# tdt_cableTester.net
KiCad netlist of a schematic drawn in EAGLE
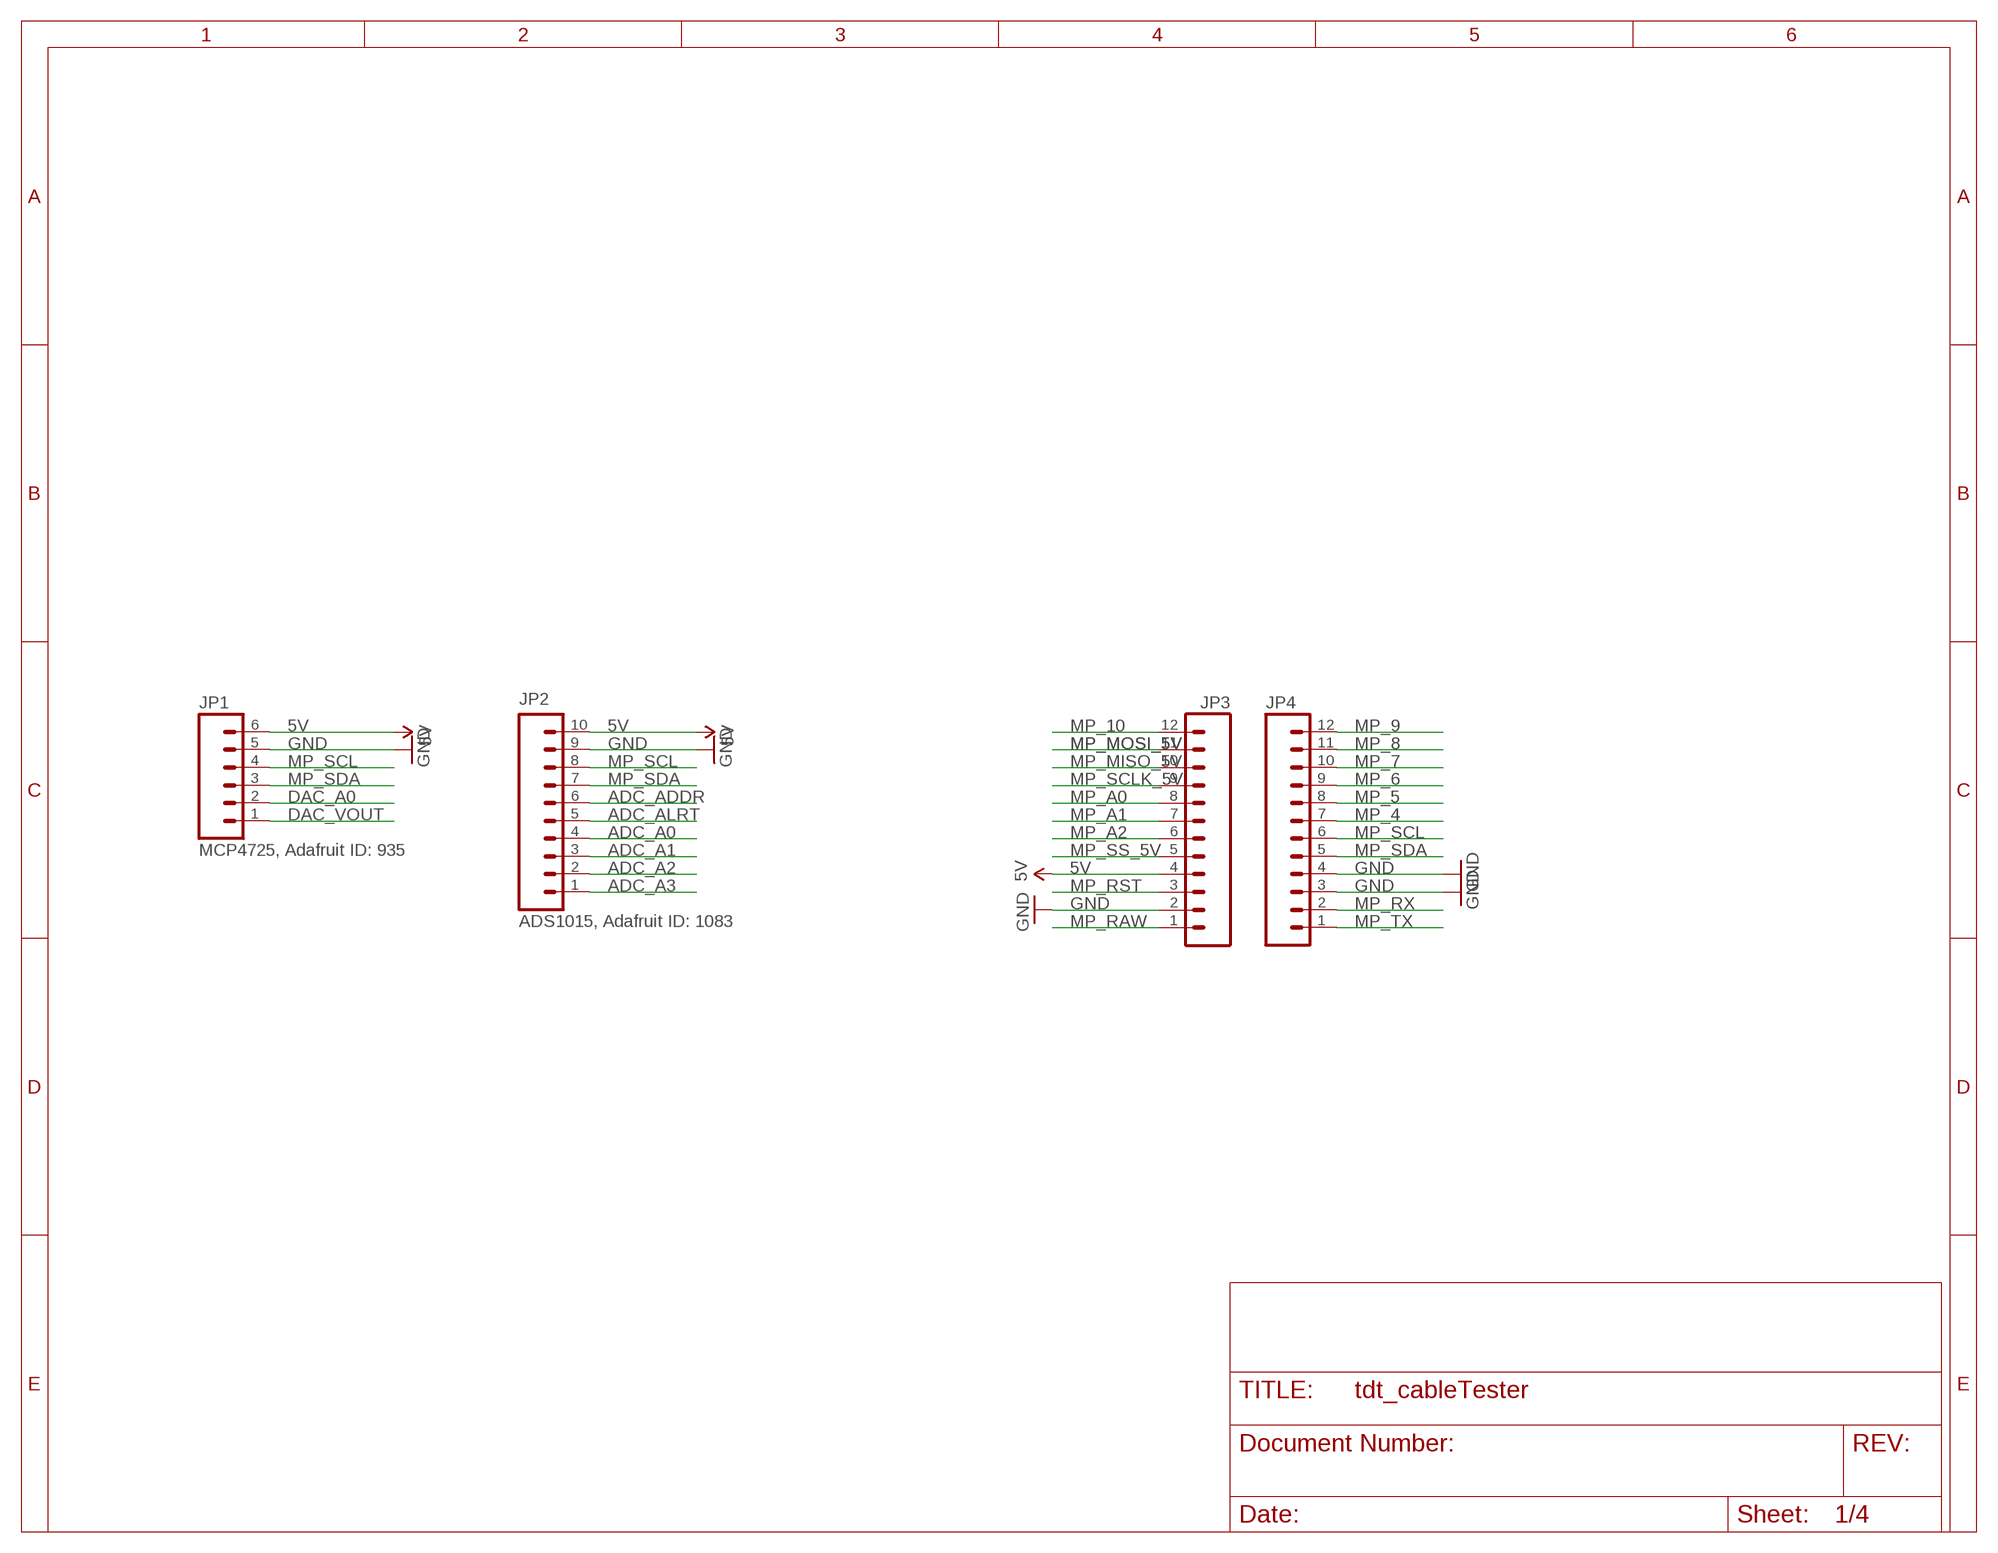
[diagram p0: schematic, sheet 1]
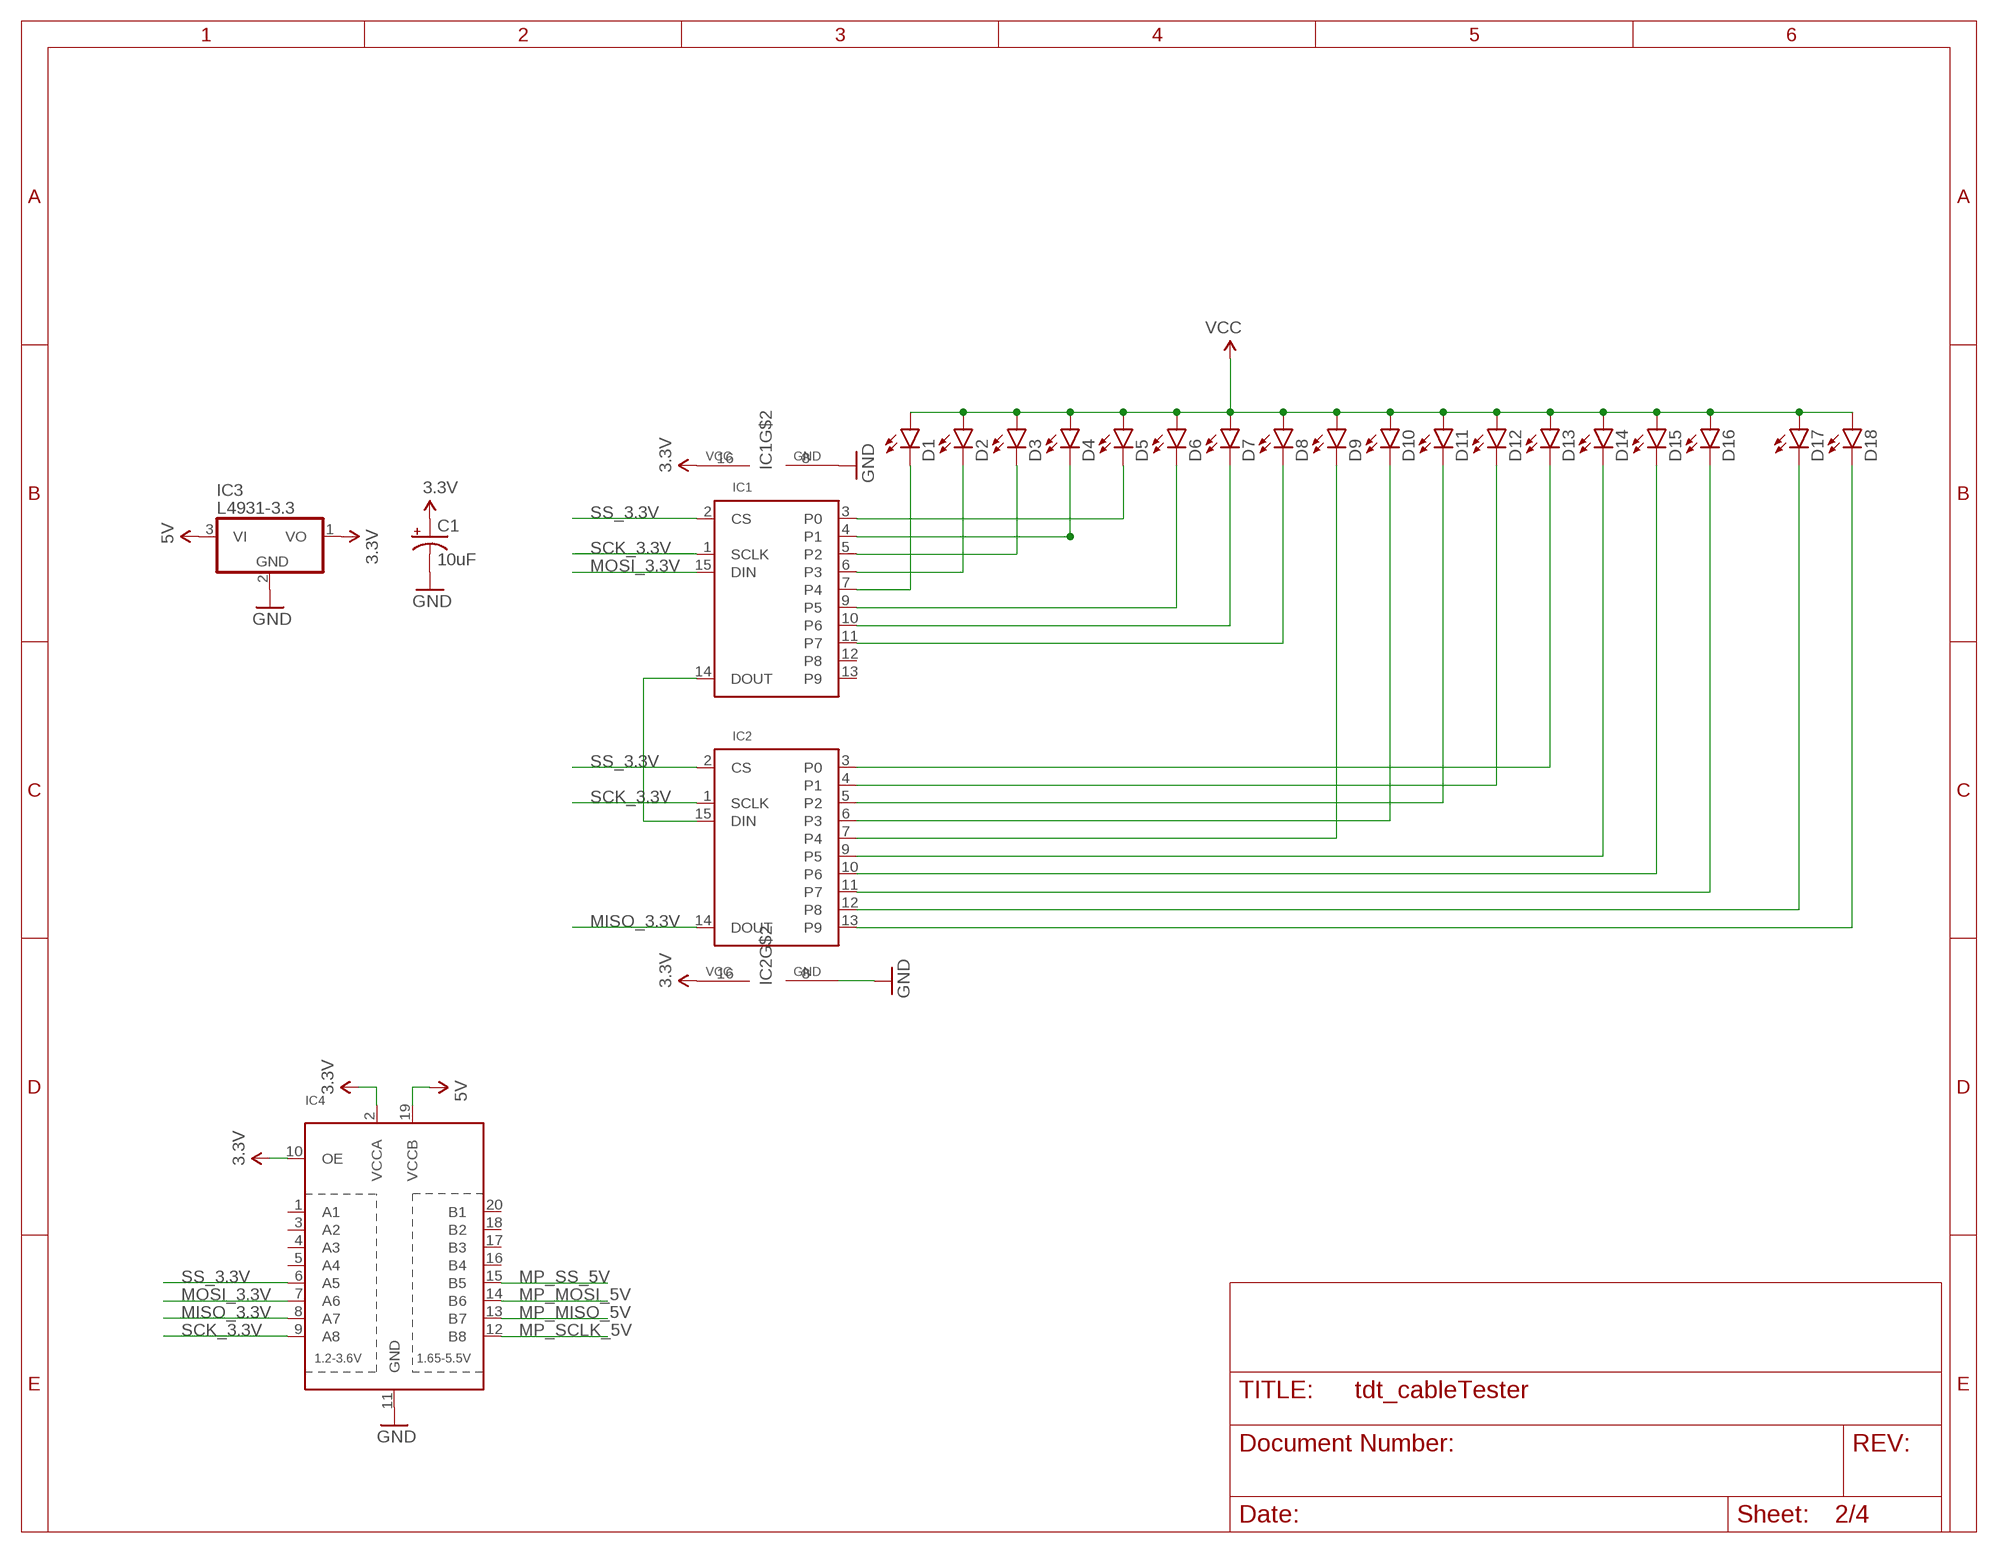
[diagram p1: schematic, sheet 2]
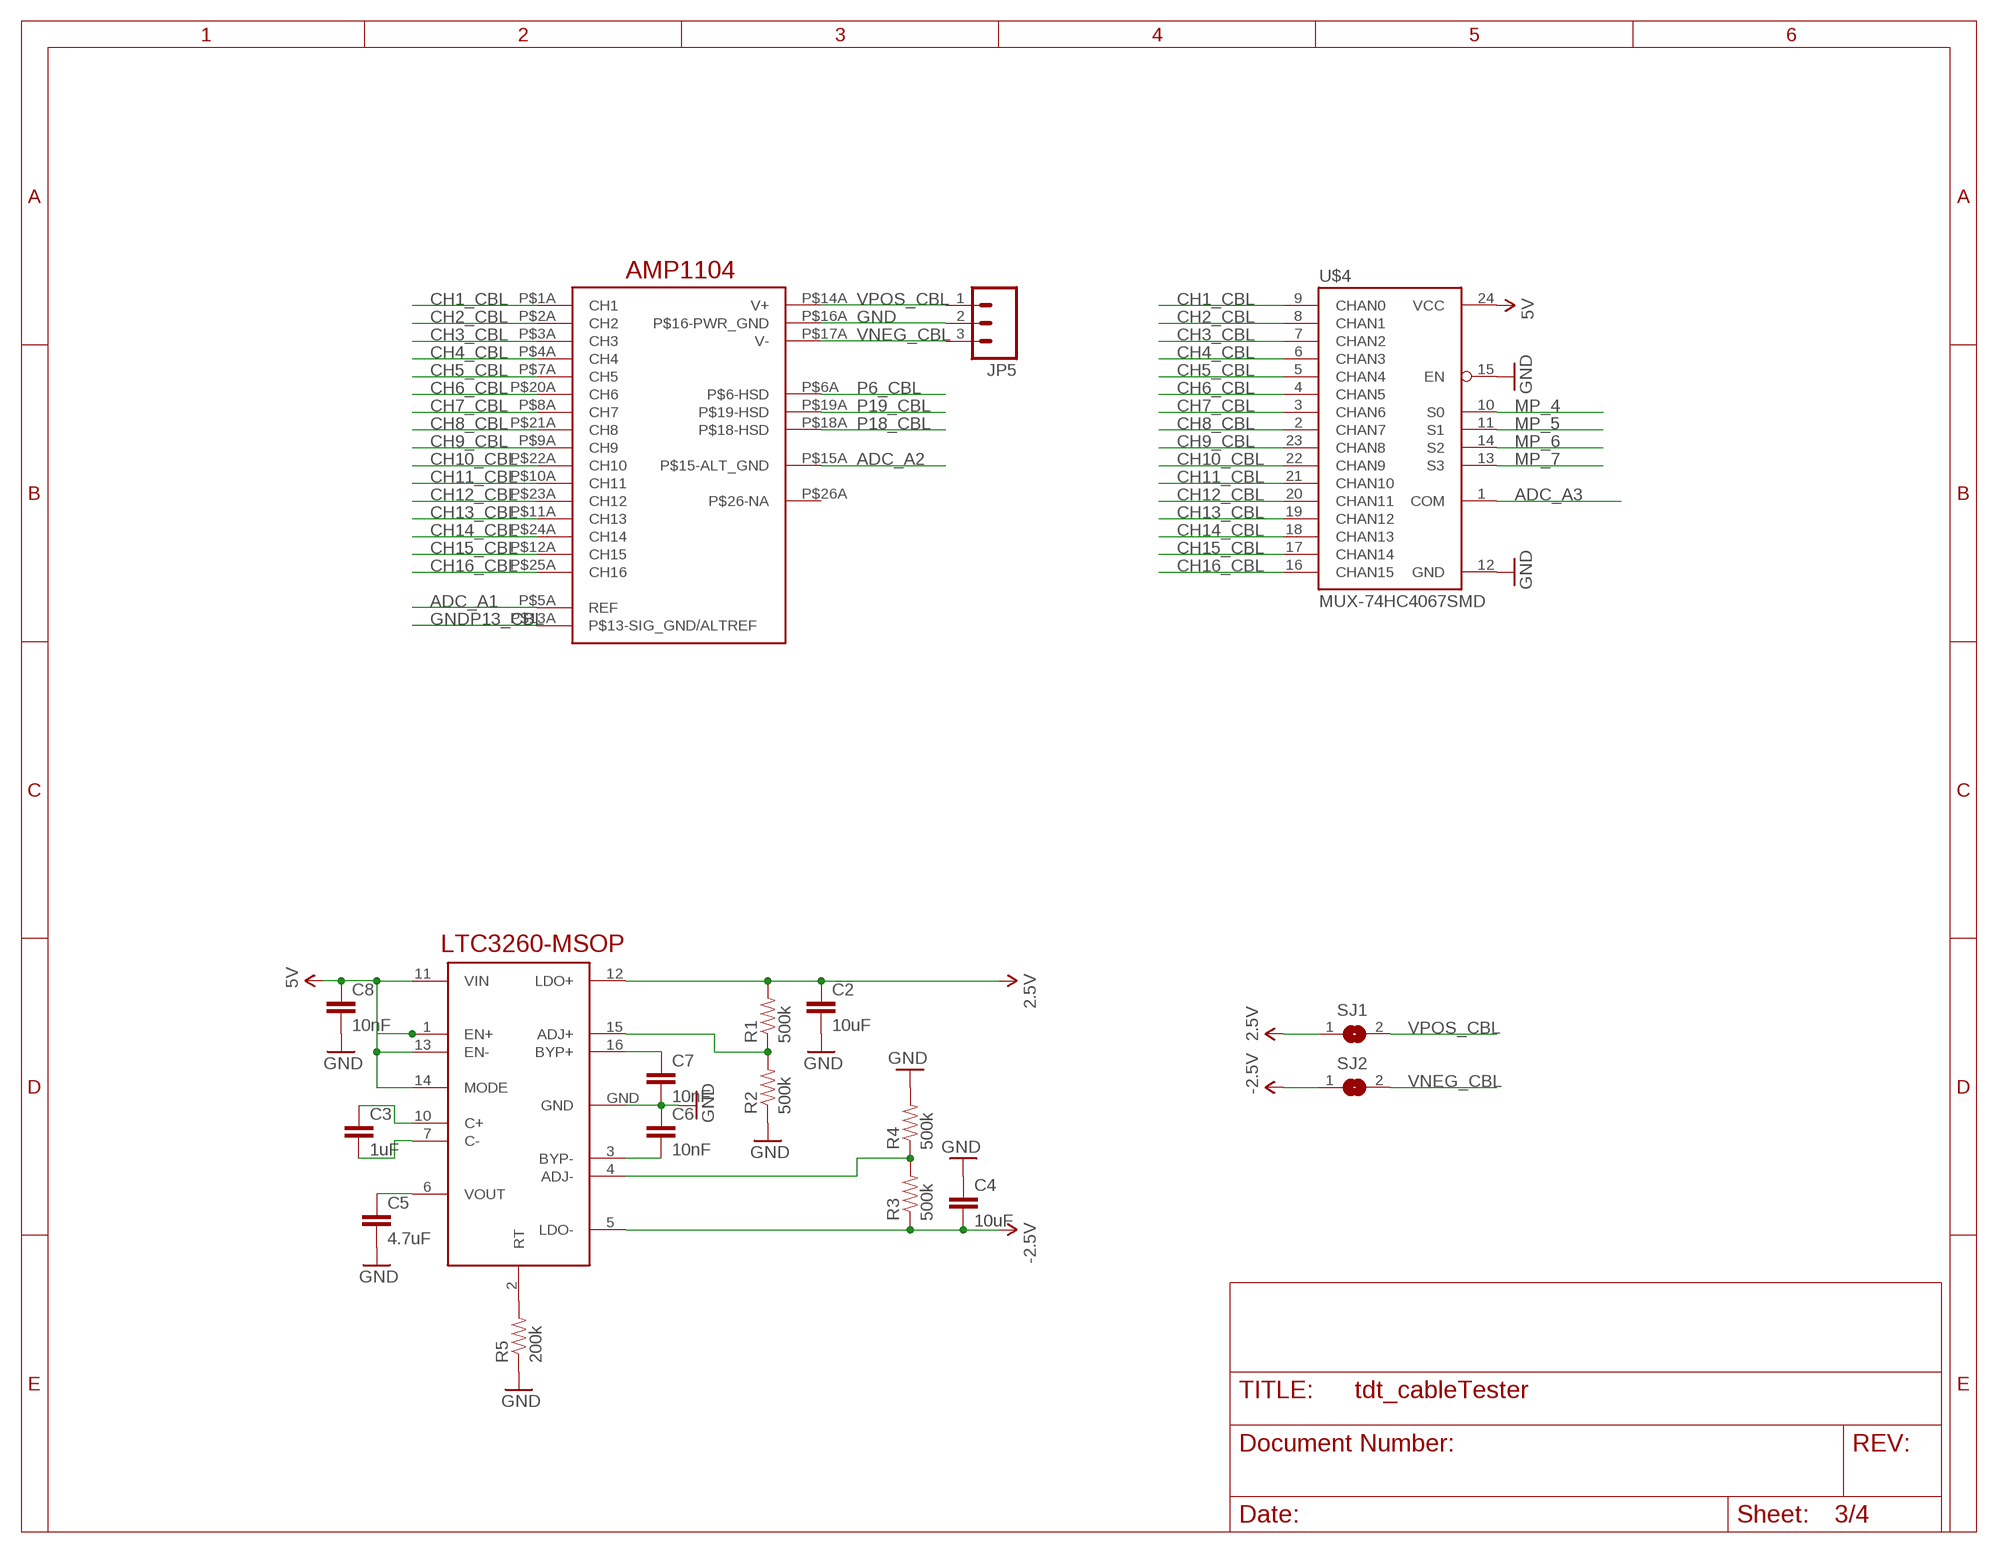
[diagram p2: schematic, sheet 3]
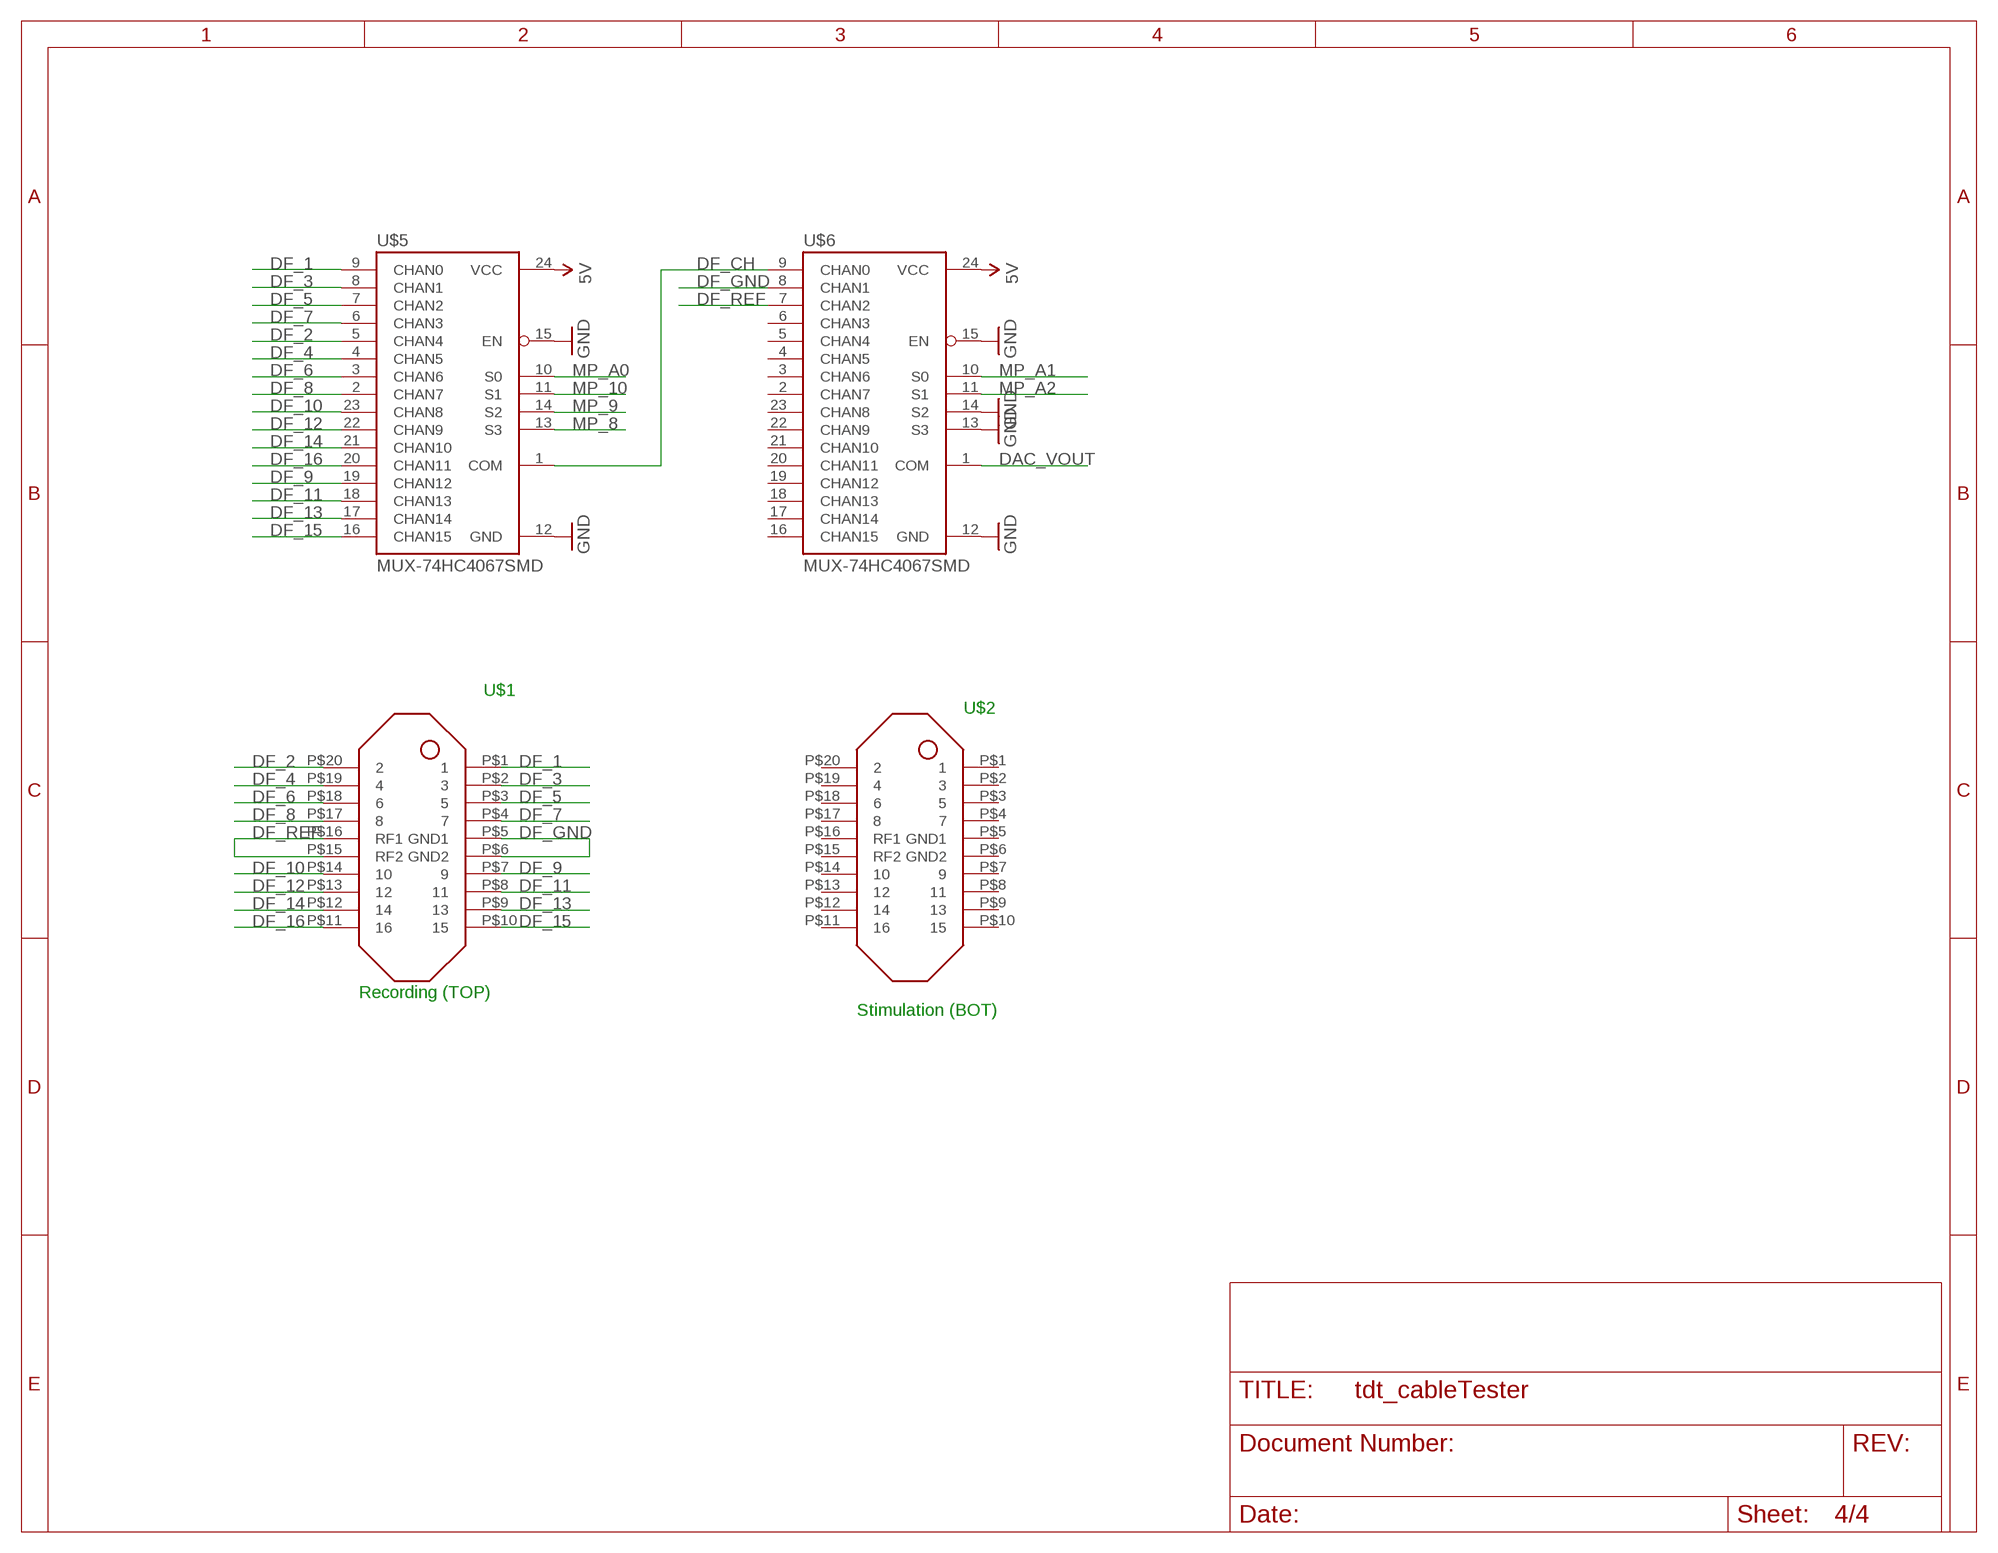
[diagram p3: schematic, sheet 4]

(export (version "E")
  (design (tool "Eeschema 10.0.6"))
  (components
    (comp (ref "JP1")
      (value "MCP4725, Adafruit ID: 935")
      (footprint "eagle-import:1X06")
      (libsource (lib "eagle-import") (part "M06SILK_FEMALE_PTH"))
    )
    (comp (ref "JP2")
      (value "ADS1015, Adafruit ID: 1083")
      (footprint "eagle-import:1X10")
      (libsource (lib "eagle-import") (part "M10SILK_FEMALE_PTH"))
    )
    (comp (ref "JP3")
      (value "M12PTH")
      (footprint "eagle-import:1X12")
      (libsource (lib "eagle-import") (part "M12PTH"))
    )
    (comp (ref "JP4")
      (value "M12PTH")
      (footprint "eagle-import:1X12")
      (libsource (lib "eagle-import") (part "M12PTH"))
    )
    (comp (ref "C1")
      (value "10uF")
      (footprint "eagle-import:CPOL-RADIAL-10UF-25V")
      (libsource (lib "eagle-import") (part "CAP_POLPTH2"))
    )
    (comp (ref "D1")
      (value "LED1206")
      (footprint "eagle-import:LED-1206")
      (libsource (lib "eagle-import") (part "LED1206"))
    )
    (comp (ref "D2")
      (value "LED1206")
      (footprint "eagle-import:LED-1206")
      (libsource (lib "eagle-import") (part "LED1206"))
    )
    (comp (ref "D3")
      (value "LED1206")
      (footprint "eagle-import:LED-1206")
      (libsource (lib "eagle-import") (part "LED1206"))
    )
    (comp (ref "D4")
      (value "LED1206")
      (footprint "eagle-import:LED-1206")
      (libsource (lib "eagle-import") (part "LED1206"))
    )
    (comp (ref "D5")
      (value "LED1206")
      (footprint "eagle-import:LED-1206")
      (libsource (lib "eagle-import") (part "LED1206"))
    )
    (comp (ref "D6")
      (value "LED1206")
      (footprint "eagle-import:LED-1206")
      (libsource (lib "eagle-import") (part "LED1206"))
    )
    (comp (ref "D7")
      (value "LED1206")
      (footprint "eagle-import:LED-1206")
      (libsource (lib "eagle-import") (part "LED1206"))
    )
    (comp (ref "D8")
      (value "LED1206")
      (footprint "eagle-import:LED-1206")
      (libsource (lib "eagle-import") (part "LED1206"))
    )
    (comp (ref "D9")
      (value "LED1206")
      (footprint "eagle-import:LED-1206")
      (libsource (lib "eagle-import") (part "LED1206"))
    )
    (comp (ref "D10")
      (value "LED1206")
      (footprint "eagle-import:LED-1206")
      (libsource (lib "eagle-import") (part "LED1206"))
    )
    (comp (ref "D11")
      (value "LED1206")
      (footprint "eagle-import:LED-1206")
      (libsource (lib "eagle-import") (part "LED1206"))
    )
    (comp (ref "D12")
      (value "LED1206")
      (footprint "eagle-import:LED-1206")
      (libsource (lib "eagle-import") (part "LED1206"))
    )
    (comp (ref "D13")
      (value "LED1206")
      (footprint "eagle-import:LED-1206")
      (libsource (lib "eagle-import") (part "LED1206"))
    )
    (comp (ref "D14")
      (value "LED1206")
      (footprint "eagle-import:LED-1206")
      (libsource (lib "eagle-import") (part "LED1206"))
    )
    (comp (ref "D15")
      (value "LED1206")
      (footprint "eagle-import:LED-1206")
      (libsource (lib "eagle-import") (part "LED1206"))
    )
    (comp (ref "D16")
      (value "LED1206")
      (footprint "eagle-import:LED-1206")
      (libsource (lib "eagle-import") (part "LED1206"))
    )
    (comp (ref "D17")
      (value "LED1206")
      (footprint "eagle-import:LED-1206")
      (libsource (lib "eagle-import") (part "LED1206"))
    )
    (comp (ref "D18")
      (value "LED1206")
      (footprint "eagle-import:LED-1206")
      (libsource (lib "eagle-import") (part "LED1206"))
    )
    (comp (ref "IC1")
      (value "MAX6966AEE")
      (footprint "eagle-import:QSOP16")
      (libsource (lib "eagle-import") (part "MAX6966AEE"))
    )
    (comp (ref "IC2")
      (value "MAX6966AEE")
      (footprint "eagle-import:QSOP16")
      (libsource (lib "eagle-import") (part "MAX6966AEE"))
    )
    (comp (ref "IC3")
      (value "L4931-3.3")
      (footprint "eagle-import:TO92")
      (libsource (lib "eagle-import") (part "78ZL05"))
    )
    (comp (ref "IC4")
      (value "TXB0108PWR")
      (footprint "eagle-import:TSSOP20")
      (libsource (lib "eagle-import") (part "TXB0108PWR"))
    )
    (comp (ref "C2")
      (value "10uF")
      (footprint "eagle-import:0805")
      (libsource (lib "eagle-import") (part "CAP0805"))
    )
    (comp (ref "C3")
      (value "1uF")
      (footprint "eagle-import:0805")
      (libsource (lib "eagle-import") (part "CAP0805"))
    )
    (comp (ref "C4")
      (value "10uF")
      (footprint "eagle-import:0805")
      (libsource (lib "eagle-import") (part "CAP0805"))
    )
    (comp (ref "C5")
      (value "4.7uF")
      (footprint "eagle-import:0805")
      (libsource (lib "eagle-import") (part "CAP0805"))
    )
    (comp (ref "C6")
      (value "10nF")
      (footprint "eagle-import:0805")
      (libsource (lib "eagle-import") (part "CAP0805"))
    )
    (comp (ref "C7")
      (value "10nF")
      (footprint "eagle-import:0805")
      (libsource (lib "eagle-import") (part "CAP0805"))
    )
    (comp (ref "C8")
      (value "10nF")
      (footprint "eagle-import:0805")
      (libsource (lib "eagle-import") (part "CAP0805"))
    )
    (comp (ref "JP5")
      (value "M03PTH")
      (footprint "eagle-import:1X03")
      (libsource (lib "eagle-import") (part "M03PTH"))
    )
    (comp (ref "R1")
      (value "500k")
      (footprint "eagle-import:0805")
      (libsource (lib "eagle-import") (part "RESISTOR0805-RES"))
    )
    (comp (ref "R2")
      (value "500k")
      (footprint "eagle-import:0805")
      (libsource (lib "eagle-import") (part "RESISTOR0805-RES"))
    )
    (comp (ref "R3")
      (value "500k")
      (footprint "eagle-import:0805")
      (libsource (lib "eagle-import") (part "RESISTOR0805-RES"))
    )
    (comp (ref "R4")
      (value "500k")
      (footprint "eagle-import:0805")
      (libsource (lib "eagle-import") (part "RESISTOR0805-RES"))
    )
    (comp (ref "R5")
      (value "200k")
      (footprint "eagle-import:0805")
      (libsource (lib "eagle-import") (part "RESISTOR0805-RES"))
    )
    (comp (ref "SJ1") (value "SJ") (footprint "eagle-import:SJ") (libsource (lib "eagle-import") (part "SJ")))
    (comp (ref "SJ2") (value "SJ") (footprint "eagle-import:SJ") (libsource (lib "eagle-import") (part "SJ")))
    (comp (ref "U$3")
      (value "AMP1104")
      (footprint "eagle-import:AMP1104")
      (libsource (lib "eagle-import") (part "AMP1104"))
    )
    (comp (ref "U$4")
      (value "MUX-74HC4067SMD")
      (footprint "eagle-import:SSOP24")
      (libsource (lib "eagle-import") (part "MUX-74HC4067SMD"))
    )
    (comp (ref "U$7")
      (value "LTC3260-MSOP")
      (footprint "eagle-import:MSOP16")
      (libsource (lib "eagle-import") (part "LTC3260-MSOP"))
    )
    (comp (ref "U$1")
      (value "DF30_HEADER")
      (footprint "eagle-import:DF30FC-20DP-0.4V")
      (libsource (lib "eagle-import") (part "DF30_HEADER"))
    )
    (comp (ref "U$2")
      (value "DF30_HEADER")
      (footprint "eagle-import:DF30FC-20DP-0.4V")
      (libsource (lib "eagle-import") (part "DF30_HEADER"))
    )
    (comp (ref "U$5")
      (value "MUX-74HC4067SMD")
      (footprint "eagle-import:SSOP24")
      (libsource (lib "eagle-import") (part "MUX-74HC4067SMD"))
    )
    (comp (ref "U$6")
      (value "MUX-74HC4067SMD")
      (footprint "eagle-import:SSOP24")
      (libsource (lib "eagle-import") (part "MUX-74HC4067SMD"))
    )
  )
  (nets
    (net (code "1") (name "-2.5V") (class "Default")
      (node (ref "C4") (pin "2") (pinfunction "2_2") (pintype "passive"))
      (node (ref "R3") (pin "1") (pinfunction "1_1") (pintype "passive"))
      (node (ref "SJ2") (pin "1") (pinfunction "1_1") (pintype "passive"))
      (node (ref "U$7") (pin "5") (pinfunction "LDO-_5") (pintype "bidirectional"))
    )
    (net (code "2") (name "2.5V") (class "Default")
      (node (ref "C2") (pin "1") (pinfunction "1_1") (pintype "passive"))
      (node (ref "R1") (pin "2") (pinfunction "2_2") (pintype "passive"))
      (node (ref "SJ1") (pin "1") (pinfunction "1_1") (pintype "passive"))
      (node (ref "U$7") (pin "12") (pinfunction "LDO+_12") (pintype "bidirectional"))
    )
    (net (code "3") (name "3.3V") (class "Default")
      (node (ref "C1") (pin "1") (pinfunction "+_1") (pintype "passive"))
      (node (ref "IC1") (pin "16") (pinfunction "VCC_16") (pintype "power_in"))
      (node (ref "IC2") (pin "16") (pinfunction "VCC_16") (pintype "power_in"))
      (node (ref "IC3") (pin "1") (pinfunction "VO_1") (pintype "passive"))
      (node (ref "IC4") (pin "10") (pinfunction "OE_10") (pintype "bidirectional"))
      (node (ref "IC4") (pin "2") (pinfunction "VCCA_2") (pintype "bidirectional"))
    )
    (net (code "4") (name "5V") (class "Default")
      (node (ref "C8") (pin "1") (pinfunction "1_1") (pintype "passive"))
      (node (ref "IC3") (pin "3") (pinfunction "VI_3") (pintype "input"))
      (node (ref "IC4") (pin "19") (pinfunction "VCCB_19") (pintype "bidirectional"))
      (node (ref "JP1") (pin "6") (pinfunction "6_6") (pintype "passive"))
      (node (ref "JP2") (pin "10") (pinfunction "10_10") (pintype "passive"))
      (node (ref "JP3") (pin "4") (pinfunction "4_4") (pintype "passive"))
      (node (ref "U$4") (pin "24") (pinfunction "VCC_24") (pintype "bidirectional"))
      (node (ref "U$5") (pin "24") (pinfunction "VCC_24") (pintype "bidirectional"))
      (node (ref "U$6") (pin "24") (pinfunction "VCC_24") (pintype "bidirectional"))
      (node (ref "U$7") (pin "1") (pinfunction "EN+_1") (pintype "bidirectional"))
      (node (ref "U$7") (pin "11") (pinfunction "VIN_11") (pintype "bidirectional"))
      (node (ref "U$7") (pin "13") (pinfunction "EN-_13") (pintype "bidirectional"))
      (node (ref "U$7") (pin "14") (pinfunction "MODE_14") (pintype "bidirectional"))
    )
    (net (code "5") (name "ADC_A0") (class "Default")
      (node (ref "JP2") (pin "4") (pinfunction "4_4") (pintype "passive"))
    )
    (net (code "6") (name "ADC_A1") (class "Default")
      (node (ref "JP2") (pin "3") (pinfunction "3_3") (pintype "passive"))
      (node (ref "U$3") (pin "P$5A") (pinfunction "REF_P$5A") (pintype "bidirectional"))
    )
    (net (code "7") (name "ADC_A2") (class "Default")
      (node (ref "JP2") (pin "2") (pinfunction "2_2") (pintype "passive"))
      (node (ref "U$3") (pin "P$15A") (pinfunction "P$15-ALT_GND_P$15A") (pintype "bidirectional"))
    )
    (net (code "8") (name "ADC_A3") (class "Default")
      (node (ref "JP2") (pin "1") (pinfunction "1_1") (pintype "passive"))
      (node (ref "U$4") (pin "1") (pinfunction "COM_1") (pintype "bidirectional"))
    )
    (net (code "9") (name "ADC_ADDR") (class "Default")
      (node (ref "JP2") (pin "6") (pinfunction "6_6") (pintype "passive"))
    )
    (net (code "10") (name "ADC_ALRT") (class "Default")
      (node (ref "JP2") (pin "5") (pinfunction "5_5") (pintype "passive"))
    )
    (net (code "11") (name "CH1_CBL") (class "Default")
      (node (ref "U$3") (pin "P$1A") (pinfunction "CH1_P$1A") (pintype "bidirectional"))
      (node (ref "U$4") (pin "9") (pinfunction "CHAN0_9") (pintype "bidirectional"))
    )
    (net (code "12") (name "CH2_CBL") (class "Default")
      (node (ref "U$3") (pin "P$2A") (pinfunction "CH2_P$2A") (pintype "bidirectional"))
      (node (ref "U$4") (pin "8") (pinfunction "CHAN1_8") (pintype "bidirectional"))
    )
    (net (code "13") (name "CH3_CBL") (class "Default")
      (node (ref "U$3") (pin "P$3A") (pinfunction "CH3_P$3A") (pintype "bidirectional"))
      (node (ref "U$4") (pin "7") (pinfunction "CHAN2_7") (pintype "bidirectional"))
    )
    (net (code "14") (name "CH4_CBL") (class "Default")
      (node (ref "U$3") (pin "P$4A") (pinfunction "CH4_P$4A") (pintype "bidirectional"))
      (node (ref "U$4") (pin "6") (pinfunction "CHAN3_6") (pintype "bidirectional"))
    )
    (net (code "15") (name "CH5_CBL") (class "Default")
      (node (ref "U$3") (pin "P$7A") (pinfunction "CH5_P$7A") (pintype "bidirectional"))
      (node (ref "U$4") (pin "5") (pinfunction "CHAN4_5") (pintype "bidirectional"))
    )
    (net (code "16") (name "CH6_CBL") (class "Default")
      (node (ref "U$3") (pin "P$20A") (pinfunction "CH6_P$20A") (pintype "bidirectional"))
      (node (ref "U$4") (pin "4") (pinfunction "CHAN5_4") (pintype "bidirectional"))
    )
    (net (code "17") (name "CH7_CBL") (class "Default")
      (node (ref "U$3") (pin "P$8A") (pinfunction "CH7_P$8A") (pintype "bidirectional"))
      (node (ref "U$4") (pin "3") (pinfunction "CHAN6_3") (pintype "bidirectional"))
    )
    (net (code "18") (name "CH8_CBL") (class "Default")
      (node (ref "U$3") (pin "P$21A") (pinfunction "CH8_P$21A") (pintype "bidirectional"))
      (node (ref "U$4") (pin "2") (pinfunction "CHAN7_2") (pintype "bidirectional"))
    )
    (net (code "19") (name "CH9_CBL") (class "Default")
      (node (ref "U$3") (pin "P$9A") (pinfunction "CH9_P$9A") (pintype "bidirectional"))
      (node (ref "U$4") (pin "23") (pinfunction "CHAN8_23") (pintype "bidirectional"))
    )
    (net (code "20") (name "CH10_CBL") (class "Default")
      (node (ref "U$3") (pin "P$22A") (pinfunction "CH10_P$22A") (pintype "bidirectional"))
      (node (ref "U$4") (pin "22") (pinfunction "CHAN9_22") (pintype "bidirectional"))
    )
    (net (code "21") (name "CH11_CBL") (class "Default")
      (node (ref "U$3") (pin "P$10A") (pinfunction "CH11_P$10A") (pintype "bidirectional"))
      (node (ref "U$4") (pin "21") (pinfunction "CHAN10_21") (pintype "bidirectional"))
    )
    (net (code "22") (name "CH12_CBL") (class "Default")
      (node (ref "U$3") (pin "P$23A") (pinfunction "CH12_P$23A") (pintype "bidirectional"))
      (node (ref "U$4") (pin "20") (pinfunction "CHAN11_20") (pintype "bidirectional"))
    )
    (net (code "23") (name "CH13_CBL") (class "Default")
      (node (ref "U$3") (pin "P$11A") (pinfunction "CH13_P$11A") (pintype "bidirectional"))
      (node (ref "U$4") (pin "19") (pinfunction "CHAN12_19") (pintype "bidirectional"))
    )
    (net (code "24") (name "CH14_CBL") (class "Default")
      (node (ref "U$3") (pin "P$24A") (pinfunction "CH14_P$24A") (pintype "bidirectional"))
      (node (ref "U$4") (pin "18") (pinfunction "CHAN13_18") (pintype "bidirectional"))
    )
    (net (code "25") (name "CH15_CBL") (class "Default")
      (node (ref "U$3") (pin "P$12A") (pinfunction "CH15_P$12A") (pintype "bidirectional"))
      (node (ref "U$4") (pin "17") (pinfunction "CHAN14_17") (pintype "bidirectional"))
    )
    (net (code "26") (name "CH16_CBL") (class "Default")
      (node (ref "U$3") (pin "P$25A") (pinfunction "CH16_P$25A") (pintype "bidirectional"))
      (node (ref "U$4") (pin "16") (pinfunction "CHAN15_16") (pintype "bidirectional"))
    )
    (net (code "27") (name "DAC_A0") (class "Default")
      (node (ref "JP1") (pin "2") (pinfunction "2_2") (pintype "passive"))
    )
    (net (code "28") (name "DAC_VOUT") (class "Default")
      (node (ref "JP1") (pin "1") (pinfunction "1_1") (pintype "passive"))
      (node (ref "U$6") (pin "1") (pinfunction "COM_1") (pintype "bidirectional"))
    )
    (net (code "29") (name "DF_1") (class "Default")
      (node (ref "U$1") (pin "P$1") (pinfunction "1_P$1") (pintype "bidirectional"))
      (node (ref "U$5") (pin "9") (pinfunction "CHAN0_9") (pintype "bidirectional"))
    )
    (net (code "30") (name "DF_2") (class "Default")
      (node (ref "U$1") (pin "P$20") (pinfunction "2_P$20") (pintype "bidirectional"))
      (node (ref "U$5") (pin "5") (pinfunction "CHAN4_5") (pintype "bidirectional"))
    )
    (net (code "31") (name "DF_3") (class "Default")
      (node (ref "U$1") (pin "P$2") (pinfunction "3_P$2") (pintype "bidirectional"))
      (node (ref "U$5") (pin "8") (pinfunction "CHAN1_8") (pintype "bidirectional"))
    )
    (net (code "32") (name "DF_4") (class "Default")
      (node (ref "U$1") (pin "P$19") (pinfunction "4_P$19") (pintype "bidirectional"))
      (node (ref "U$5") (pin "4") (pinfunction "CHAN5_4") (pintype "bidirectional"))
    )
    (net (code "33") (name "DF_5") (class "Default")
      (node (ref "U$1") (pin "P$3") (pinfunction "5_P$3") (pintype "bidirectional"))
      (node (ref "U$5") (pin "7") (pinfunction "CHAN2_7") (pintype "bidirectional"))
    )
    (net (code "34") (name "DF_6") (class "Default")
      (node (ref "U$1") (pin "P$18") (pinfunction "6_P$18") (pintype "bidirectional"))
      (node (ref "U$5") (pin "3") (pinfunction "CHAN6_3") (pintype "bidirectional"))
    )
    (net (code "35") (name "DF_7") (class "Default")
      (node (ref "U$1") (pin "P$4") (pinfunction "7_P$4") (pintype "bidirectional"))
      (node (ref "U$5") (pin "6") (pinfunction "CHAN3_6") (pintype "bidirectional"))
    )
    (net (code "36") (name "DF_8") (class "Default")
      (node (ref "U$1") (pin "P$17") (pinfunction "8_P$17") (pintype "bidirectional"))
      (node (ref "U$5") (pin "2") (pinfunction "CHAN7_2") (pintype "bidirectional"))
    )
    (net (code "37") (name "DF_9") (class "Default")
      (node (ref "U$1") (pin "P$7") (pinfunction "9_P$7") (pintype "bidirectional"))
      (node (ref "U$5") (pin "19") (pinfunction "CHAN12_19") (pintype "bidirectional"))
    )
    (net (code "38") (name "DF_10") (class "Default")
      (node (ref "U$1") (pin "P$14") (pinfunction "10_P$14") (pintype "bidirectional"))
      (node (ref "U$5") (pin "23") (pinfunction "CHAN8_23") (pintype "bidirectional"))
    )
    (net (code "39") (name "DF_11") (class "Default")
      (node (ref "U$1") (pin "P$8") (pinfunction "11_P$8") (pintype "bidirectional"))
      (node (ref "U$5") (pin "18") (pinfunction "CHAN13_18") (pintype "bidirectional"))
    )
    (net (code "40") (name "DF_12") (class "Default")
      (node (ref "U$1") (pin "P$13") (pinfunction "12_P$13") (pintype "bidirectional"))
      (node (ref "U$5") (pin "22") (pinfunction "CHAN9_22") (pintype "bidirectional"))
    )
    (net (code "41") (name "DF_13") (class "Default")
      (node (ref "U$1") (pin "P$9") (pinfunction "13_P$9") (pintype "bidirectional"))
      (node (ref "U$5") (pin "17") (pinfunction "CHAN14_17") (pintype "bidirectional"))
    )
    (net (code "42") (name "DF_14") (class "Default")
      (node (ref "U$1") (pin "P$12") (pinfunction "14_P$12") (pintype "bidirectional"))
      (node (ref "U$5") (pin "21") (pinfunction "CHAN10_21") (pintype "bidirectional"))
    )
    (net (code "43") (name "DF_15") (class "Default")
      (node (ref "U$1") (pin "P$10") (pinfunction "15_P$10") (pintype "bidirectional"))
      (node (ref "U$5") (pin "16") (pinfunction "CHAN15_16") (pintype "bidirectional"))
    )
    (net (code "44") (name "DF_16") (class "Default")
      (node (ref "U$1") (pin "P$11") (pinfunction "16_P$11") (pintype "bidirectional"))
      (node (ref "U$5") (pin "20") (pinfunction "CHAN11_20") (pintype "bidirectional"))
    )
    (net (code "45") (name "DF_CH") (class "Default")
      (node (ref "U$5") (pin "1") (pinfunction "COM_1") (pintype "bidirectional"))
      (node (ref "U$6") (pin "9") (pinfunction "CHAN0_9") (pintype "bidirectional"))
    )
    (net (code "46") (name "DF_GND") (class "Default")
      (node (ref "U$1") (pin "P$5") (pinfunction "GND1_P$5") (pintype "bidirectional"))
      (node (ref "U$1") (pin "P$6") (pinfunction "GND2_P$6") (pintype "bidirectional"))
      (node (ref "U$6") (pin "8") (pinfunction "CHAN1_8") (pintype "bidirectional"))
    )
    (net (code "47") (name "DF_REF") (class "Default")
      (node (ref "U$1") (pin "P$15") (pinfunction "RF2_P$15") (pintype "bidirectional"))
      (node (ref "U$1") (pin "P$16") (pinfunction "RF1_P$16") (pintype "bidirectional"))
      (node (ref "U$6") (pin "7") (pinfunction "CHAN2_7") (pintype "bidirectional"))
    )
    (net (code "48") (name "GND") (class "Default")
      (node (ref "C1") (pin "2") (pinfunction "-_2") (pintype "passive"))
      (node (ref "C2") (pin "2") (pinfunction "2_2") (pintype "passive"))
      (node (ref "C4") (pin "1") (pinfunction "1_1") (pintype "passive"))
      (node (ref "C5") (pin "2") (pinfunction "2_2") (pintype "passive"))
      (node (ref "C6") (pin "1") (pinfunction "1_1") (pintype "passive"))
      (node (ref "C7") (pin "2") (pinfunction "2_2") (pintype "passive"))
      (node (ref "C8") (pin "2") (pinfunction "2_2") (pintype "passive"))
      (node (ref "IC1") (pin "8") (pinfunction "GND_8") (pintype "power_in"))
      (node (ref "IC2") (pin "8") (pinfunction "GND_8") (pintype "power_in"))
      (node (ref "IC3") (pin "2") (pinfunction "GND_2") (pintype "passive"))
      (node (ref "IC4") (pin "11") (pinfunction "GND_11") (pintype "bidirectional"))
      (node (ref "JP1") (pin "5") (pinfunction "5_5") (pintype "passive"))
      (node (ref "JP2") (pin "9") (pinfunction "9_9") (pintype "passive"))
      (node (ref "JP3") (pin "2") (pinfunction "2_2") (pintype "passive"))
      (node (ref "JP4") (pin "3") (pinfunction "3_3") (pintype "passive"))
      (node (ref "JP4") (pin "4") (pinfunction "4_4") (pintype "passive"))
      (node (ref "JP5") (pin "2") (pinfunction "2_2") (pintype "passive"))
      (node (ref "R2") (pin "1") (pinfunction "1_1") (pintype "passive"))
      (node (ref "R4") (pin "2") (pinfunction "2_2") (pintype "passive"))
      (node (ref "R5") (pin "1") (pinfunction "1_1") (pintype "passive"))
      (node (ref "U$3") (pin "P$16A") (pinfunction "P$16-PWR_GND_P$16A") (pintype "bidirectional"))
      (node (ref "U$4") (pin "12") (pinfunction "GND_12") (pintype "bidirectional"))
      (node (ref "U$4") (pin "15") (pinfunction "EN_15") (pintype "input"))
      (node (ref "U$5") (pin "12") (pinfunction "GND_12") (pintype "bidirectional"))
      (node (ref "U$5") (pin "15") (pinfunction "EN_15") (pintype "input"))
      (node (ref "U$6") (pin "12") (pinfunction "GND_12") (pintype "bidirectional"))
      (node (ref "U$6") (pin "13") (pinfunction "S3_13") (pintype "input"))
      (node (ref "U$6") (pin "14") (pinfunction "S2_14") (pintype "input"))
      (node (ref "U$6") (pin "15") (pinfunction "EN_15") (pintype "input"))
      (node (ref "U$7") (pin "GND") (pinfunction "GND_GND") (pintype "bidirectional"))
    )
    (net (code "49") (name "GNDP13_CBL") (class "Default")
      (node (ref "U$3") (pin "P$13A") (pinfunction "P$13-SIG_GND/ALTREF_P$13A") (pintype "bidirectional"))
    )
    (net (code "50") (name "MISO_3.3V") (class "Default")
      (node (ref "IC2") (pin "14") (pinfunction "DOUT_14") (pintype "output"))
      (node (ref "IC4") (pin "8") (pinfunction "A7_8") (pintype "bidirectional"))
    )
    (net (code "51") (name "MOSI_3.3V") (class "Default")
      (node (ref "IC1") (pin "15") (pinfunction "DIN_15") (pintype "input"))
      (node (ref "IC4") (pin "7") (pinfunction "A6_7") (pintype "bidirectional"))
    )
    (net (code "52") (name "MP_4") (class "Default")
      (node (ref "JP4") (pin "7") (pinfunction "7_7") (pintype "passive"))
      (node (ref "U$4") (pin "10") (pinfunction "S0_10") (pintype "input"))
    )
    (net (code "53") (name "MP_5") (class "Default")
      (node (ref "JP4") (pin "8") (pinfunction "8_8") (pintype "passive"))
      (node (ref "U$4") (pin "11") (pinfunction "S1_11") (pintype "input"))
    )
    (net (code "54") (name "MP_6") (class "Default")
      (node (ref "JP4") (pin "9") (pinfunction "9_9") (pintype "passive"))
      (node (ref "U$4") (pin "14") (pinfunction "S2_14") (pintype "input"))
    )
    (net (code "55") (name "MP_7") (class "Default")
      (node (ref "JP4") (pin "10") (pinfunction "10_10") (pintype "passive"))
      (node (ref "U$4") (pin "13") (pinfunction "S3_13") (pintype "input"))
    )
    (net (code "56") (name "MP_8") (class "Default")
      (node (ref "JP4") (pin "11") (pinfunction "11_11") (pintype "passive"))
      (node (ref "U$5") (pin "13") (pinfunction "S3_13") (pintype "input"))
    )
    (net (code "57") (name "MP_9") (class "Default")
      (node (ref "JP4") (pin "12") (pinfunction "12_12") (pintype "passive"))
      (node (ref "U$5") (pin "14") (pinfunction "S2_14") (pintype "input"))
    )
    (net (code "58") (name "MP_10") (class "Default")
      (node (ref "JP3") (pin "12") (pinfunction "12_12") (pintype "passive"))
      (node (ref "U$5") (pin "11") (pinfunction "S1_11") (pintype "input"))
    )
    (net (code "59") (name "MP_A0") (class "Default")
      (node (ref "JP3") (pin "8") (pinfunction "8_8") (pintype "passive"))
      (node (ref "U$5") (pin "10") (pinfunction "S0_10") (pintype "input"))
    )
    (net (code "60") (name "MP_A1") (class "Default")
      (node (ref "JP3") (pin "7") (pinfunction "7_7") (pintype "passive"))
      (node (ref "U$6") (pin "10") (pinfunction "S0_10") (pintype "input"))
    )
    (net (code "61") (name "MP_A2") (class "Default")
      (node (ref "JP3") (pin "6") (pinfunction "6_6") (pintype "passive"))
      (node (ref "U$6") (pin "11") (pinfunction "S1_11") (pintype "input"))
    )
    (net (code "62") (name "MP_MISO_5V") (class "Default")
      (node (ref "IC4") (pin "13") (pinfunction "B7_13") (pintype "bidirectional"))
      (node (ref "JP3") (pin "10") (pinfunction "10_10") (pintype "passive"))
    )
    (net (code "63") (name "MP_MOSI_5V") (class "Default")
      (node (ref "IC4") (pin "14") (pinfunction "B6_14") (pintype "bidirectional"))
      (node (ref "JP3") (pin "11") (pinfunction "11_11") (pintype "passive"))
    )
    (net (code "64") (name "MP_RAW") (class "Default")
      (node (ref "JP3") (pin "1") (pinfunction "1_1") (pintype "passive"))
    )
    (net (code "65") (name "MP_RST") (class "Default")
      (node (ref "JP3") (pin "3") (pinfunction "3_3") (pintype "passive"))
    )
    (net (code "66") (name "MP_RX") (class "Default")
      (node (ref "JP4") (pin "2") (pinfunction "2_2") (pintype "passive"))
    )
    (net (code "67") (name "MP_SCL") (class "Default")
      (node (ref "JP1") (pin "4") (pinfunction "4_4") (pintype "passive"))
      (node (ref "JP2") (pin "8") (pinfunction "8_8") (pintype "passive"))
      (node (ref "JP4") (pin "6") (pinfunction "6_6") (pintype "passive"))
    )
    (net (code "68") (name "MP_SCLK_5V") (class "Default")
      (node (ref "IC4") (pin "12") (pinfunction "B8_12") (pintype "bidirectional"))
      (node (ref "JP3") (pin "9") (pinfunction "9_9") (pintype "passive"))
    )
    (net (code "69") (name "MP_SDA") (class "Default")
      (node (ref "JP1") (pin "3") (pinfunction "3_3") (pintype "passive"))
      (node (ref "JP2") (pin "7") (pinfunction "7_7") (pintype "passive"))
      (node (ref "JP4") (pin "5") (pinfunction "5_5") (pintype "passive"))
    )
    (net (code "70") (name "MP_SS_5V") (class "Default")
      (node (ref "IC4") (pin "15") (pinfunction "B5_15") (pintype "bidirectional"))
      (node (ref "JP3") (pin "5") (pinfunction "5_5") (pintype "passive"))
    )
    (net (code "71") (name "MP_TX") (class "Default")
      (node (ref "JP4") (pin "1") (pinfunction "1_1") (pintype "passive"))
    )
    (net (code "72") (name "Net-(IC1A-DOUT)") (class "Default")
      (node (ref "IC1") (pin "14") (pinfunction "DOUT_14") (pintype "output"))
      (node (ref "IC2") (pin "15") (pinfunction "DIN_15") (pintype "input"))
    )
    (net (code "73") (name "Net-(IC1A-P0)") (class "Default")
      (node (ref "D5") (pin "C") (pinfunction "C_C") (pintype "passive"))
      (node (ref "IC1") (pin "3") (pinfunction "P0_3") (pintype "output"))
    )
    (net (code "74") (name "Net-(IC1A-P1)") (class "Default")
      (node (ref "D4") (pin "C") (pinfunction "C_C") (pintype "passive"))
      (node (ref "IC1") (pin "4") (pinfunction "P1_4") (pintype "output"))
    )
    (net (code "75") (name "Net-(IC1A-P2)") (class "Default")
      (node (ref "D3") (pin "C") (pinfunction "C_C") (pintype "passive"))
      (node (ref "IC1") (pin "5") (pinfunction "P2_5") (pintype "output"))
    )
    (net (code "76") (name "Net-(IC1A-P3)") (class "Default")
      (node (ref "D2") (pin "C") (pinfunction "C_C") (pintype "passive"))
      (node (ref "IC1") (pin "6") (pinfunction "P3_6") (pintype "output"))
    )
    (net (code "77") (name "Net-(IC1A-P4)") (class "Default")
      (node (ref "D1") (pin "C") (pinfunction "C_C") (pintype "passive"))
      (node (ref "IC1") (pin "7") (pinfunction "P4_7") (pintype "output"))
    )
    (net (code "78") (name "Net-(IC1A-P5)") (class "Default")
      (node (ref "D6") (pin "C") (pinfunction "C_C") (pintype "passive"))
      (node (ref "IC1") (pin "9") (pinfunction "P5_9") (pintype "output"))
    )
    (net (code "79") (name "Net-(IC1A-P6)") (class "Default")
      (node (ref "D7") (pin "C") (pinfunction "C_C") (pintype "passive"))
      (node (ref "IC1") (pin "10") (pinfunction "P6_10") (pintype "output"))
    )
    (net (code "80") (name "Net-(IC1A-P7)") (class "Default")
      (node (ref "D8") (pin "C") (pinfunction "C_C") (pintype "passive"))
      (node (ref "IC1") (pin "11") (pinfunction "P7_11") (pintype "output"))
    )
    (net (code "81") (name "Net-(IC2A-P0)") (class "Default")
      (node (ref "D13") (pin "C") (pinfunction "C_C") (pintype "passive"))
      (node (ref "IC2") (pin "3") (pinfunction "P0_3") (pintype "output"))
    )
    (net (code "82") (name "Net-(IC2A-P1)") (class "Default")
      (node (ref "D12") (pin "C") (pinfunction "C_C") (pintype "passive"))
      (node (ref "IC2") (pin "4") (pinfunction "P1_4") (pintype "output"))
    )
    (net (code "83") (name "Net-(IC2A-P2)") (class "Default")
      (node (ref "D11") (pin "C") (pinfunction "C_C") (pintype "passive"))
      (node (ref "IC2") (pin "5") (pinfunction "P2_5") (pintype "output"))
    )
    (net (code "84") (name "Net-(IC2A-P3)") (class "Default")
      (node (ref "D10") (pin "C") (pinfunction "C_C") (pintype "passive"))
      (node (ref "IC2") (pin "6") (pinfunction "P3_6") (pintype "output"))
    )
    (net (code "85") (name "Net-(IC2A-P4)") (class "Default")
      (node (ref "D9") (pin "C") (pinfunction "C_C") (pintype "passive"))
      (node (ref "IC2") (pin "7") (pinfunction "P4_7") (pintype "output"))
    )
    (net (code "86") (name "Net-(IC2A-P5)") (class "Default")
      (node (ref "D14") (pin "C") (pinfunction "C_C") (pintype "passive"))
      (node (ref "IC2") (pin "9") (pinfunction "P5_9") (pintype "output"))
    )
    (net (code "87") (name "Net-(IC2A-P6)") (class "Default")
      (node (ref "D15") (pin "C") (pinfunction "C_C") (pintype "passive"))
      (node (ref "IC2") (pin "10") (pinfunction "P6_10") (pintype "output"))
    )
    (net (code "88") (name "Net-(IC2A-P7)") (class "Default")
      (node (ref "D16") (pin "C") (pinfunction "C_C") (pintype "passive"))
      (node (ref "IC2") (pin "11") (pinfunction "P7_11") (pintype "output"))
    )
    (net (code "89") (name "Net-(IC2A-P8)") (class "Default")
      (node (ref "D17") (pin "C") (pinfunction "C_C") (pintype "passive"))
      (node (ref "IC2") (pin "12") (pinfunction "P8_12") (pintype "output"))
    )
    (net (code "90") (name "Net-(IC2A-P9)") (class "Default")
      (node (ref "D18") (pin "C") (pinfunction "C_C") (pintype "passive"))
      (node (ref "IC2") (pin "13") (pinfunction "P9_13") (pintype "output"))
    )
    (net (code "91") (name "Net-(U$7-ADJ+)") (class "Default")
      (node (ref "R1") (pin "1") (pinfunction "1_1") (pintype "passive"))
      (node (ref "R2") (pin "2") (pinfunction "2_2") (pintype "passive"))
      (node (ref "U$7") (pin "15") (pinfunction "ADJ+_15") (pintype "bidirectional"))
    )
    (net (code "92") (name "Net-(U$7-ADJ-)") (class "Default")
      (node (ref "R3") (pin "2") (pinfunction "2_2") (pintype "passive"))
      (node (ref "R4") (pin "1") (pinfunction "1_1") (pintype "passive"))
      (node (ref "U$7") (pin "4") (pinfunction "ADJ-_4") (pintype "bidirectional"))
    )
    (net (code "93") (name "Net-(U$7-BYP+)") (class "Default")
      (node (ref "C7") (pin "1") (pinfunction "1_1") (pintype "passive"))
      (node (ref "U$7") (pin "16") (pinfunction "BYP+_16") (pintype "bidirectional"))
    )
    (net (code "94") (name "Net-(U$7-BYP-)") (class "Default")
      (node (ref "C6") (pin "2") (pinfunction "2_2") (pintype "passive"))
      (node (ref "U$7") (pin "3") (pinfunction "BYP-_3") (pintype "bidirectional"))
    )
    (net (code "95") (name "Net-(U$7-C+)") (class "Default")
      (node (ref "C3") (pin "1") (pinfunction "1_1") (pintype "passive"))
      (node (ref "U$7") (pin "10") (pinfunction "C+_10") (pintype "bidirectional"))
    )
    (net (code "96") (name "Net-(U$7-C-)") (class "Default")
      (node (ref "C3") (pin "2") (pinfunction "2_2") (pintype "passive"))
      (node (ref "U$7") (pin "7") (pinfunction "C-_7") (pintype "bidirectional"))
    )
    (net (code "97") (name "Net-(U$7-RT)") (class "Default")
      (node (ref "R5") (pin "2") (pinfunction "2_2") (pintype "passive"))
      (node (ref "U$7") (pin "2") (pinfunction "RT_2") (pintype "bidirectional"))
    )
    (net (code "98") (name "Net-(U$7-VOUT)") (class "Default")
      (node (ref "C5") (pin "1") (pinfunction "1_1") (pintype "passive"))
      (node (ref "U$7") (pin "6") (pinfunction "VOUT_6") (pintype "bidirectional"))
    )
    (net (code "99") (name "P6_CBL") (class "Default")
      (node (ref "U$3") (pin "P$6A") (pinfunction "P$6-HSD_P$6A") (pintype "bidirectional"))
    )
    (net (code "100") (name "P18_CBL") (class "Default")
      (node (ref "U$3") (pin "P$18A") (pinfunction "P$18-HSD_P$18A") (pintype "bidirectional"))
    )
    (net (code "101") (name "P19_CBL") (class "Default")
      (node (ref "U$3") (pin "P$19A") (pinfunction "P$19-HSD_P$19A") (pintype "bidirectional"))
    )
    (net (code "102") (name "SCK_3.3V") (class "Default")
      (node (ref "IC1") (pin "1") (pinfunction "SCLK_1") (pintype "input"))
      (node (ref "IC2") (pin "1") (pinfunction "SCLK_1") (pintype "input"))
      (node (ref "IC4") (pin "9") (pinfunction "A8_9") (pintype "bidirectional"))
    )
    (net (code "103") (name "SS_3.3V") (class "Default")
      (node (ref "IC1") (pin "2") (pinfunction "CS_2") (pintype "input"))
      (node (ref "IC2") (pin "2") (pinfunction "CS_2") (pintype "input"))
      (node (ref "IC4") (pin "6") (pinfunction "A5_6") (pintype "bidirectional"))
    )
    (net (code "104") (name "VCC") (class "Default")
      (node (ref "D1") (pin "A") (pinfunction "A_A") (pintype "passive"))
      (node (ref "D10") (pin "A") (pinfunction "A_A") (pintype "passive"))
      (node (ref "D11") (pin "A") (pinfunction "A_A") (pintype "passive"))
      (node (ref "D12") (pin "A") (pinfunction "A_A") (pintype "passive"))
      (node (ref "D13") (pin "A") (pinfunction "A_A") (pintype "passive"))
      (node (ref "D14") (pin "A") (pinfunction "A_A") (pintype "passive"))
      (node (ref "D15") (pin "A") (pinfunction "A_A") (pintype "passive"))
      (node (ref "D16") (pin "A") (pinfunction "A_A") (pintype "passive"))
      (node (ref "D17") (pin "A") (pinfunction "A_A") (pintype "passive"))
      (node (ref "D18") (pin "A") (pinfunction "A_A") (pintype "passive"))
      (node (ref "D2") (pin "A") (pinfunction "A_A") (pintype "passive"))
      (node (ref "D3") (pin "A") (pinfunction "A_A") (pintype "passive"))
      (node (ref "D4") (pin "A") (pinfunction "A_A") (pintype "passive"))
      (node (ref "D5") (pin "A") (pinfunction "A_A") (pintype "passive"))
      (node (ref "D6") (pin "A") (pinfunction "A_A") (pintype "passive"))
      (node (ref "D7") (pin "A") (pinfunction "A_A") (pintype "passive"))
      (node (ref "D8") (pin "A") (pinfunction "A_A") (pintype "passive"))
      (node (ref "D9") (pin "A") (pinfunction "A_A") (pintype "passive"))
    )
    (net (code "105") (name "VNEG_CBL") (class "Default")
      (node (ref "JP5") (pin "3") (pinfunction "3_3") (pintype "passive"))
      (node (ref "SJ2") (pin "2") (pinfunction "2_2") (pintype "passive"))
      (node (ref "U$3") (pin "P$17A") (pinfunction "V-_P$17A") (pintype "bidirectional"))
    )
    (net (code "106") (name "VPOS_CBL") (class "Default")
      (node (ref "JP5") (pin "1") (pinfunction "1_1") (pintype "passive"))
      (node (ref "SJ1") (pin "2") (pinfunction "2_2") (pintype "passive"))
      (node (ref "U$3") (pin "P$14A") (pinfunction "V+_P$14A") (pintype "bidirectional"))
    )
    (net (code "107") (name "unconnected-(IC1A-P8-Pad12)") (class "Default")
      (node (ref "IC1") (pin "12") (pinfunction "P8_12") (pintype "output"))
    )
    (net (code "108") (name "unconnected-(IC1A-P9-Pad13)") (class "Default")
      (node (ref "IC1") (pin "13") (pinfunction "P9_13") (pintype "output"))
    )
    (net (code "109") (name "unconnected-(IC4-A1-Pad1)") (class "Default")
      (node (ref "IC4") (pin "1") (pinfunction "A1_1") (pintype "bidirectional"))
    )
    (net (code "110") (name "unconnected-(IC4-A2-Pad3)") (class "Default")
      (node (ref "IC4") (pin "3") (pinfunction "A2_3") (pintype "bidirectional"))
    )
    (net (code "111") (name "unconnected-(IC4-A3-Pad4)") (class "Default")
      (node (ref "IC4") (pin "4") (pinfunction "A3_4") (pintype "bidirectional"))
    )
    (net (code "112") (name "unconnected-(IC4-A4-Pad5)") (class "Default")
      (node (ref "IC4") (pin "5") (pinfunction "A4_5") (pintype "bidirectional"))
    )
    (net (code "113") (name "unconnected-(IC4-B1-Pad20)") (class "Default")
      (node (ref "IC4") (pin "20") (pinfunction "B1_20") (pintype "bidirectional"))
    )
    (net (code "114") (name "unconnected-(IC4-B2-Pad18)") (class "Default")
      (node (ref "IC4") (pin "18") (pinfunction "B2_18") (pintype "bidirectional"))
    )
    (net (code "115") (name "unconnected-(IC4-B3-Pad17)") (class "Default")
      (node (ref "IC4") (pin "17") (pinfunction "B3_17") (pintype "bidirectional"))
    )
    (net (code "116") (name "unconnected-(IC4-B4-Pad16)") (class "Default")
      (node (ref "IC4") (pin "16") (pinfunction "B4_16") (pintype "bidirectional"))
    )
    (net (code "117") (name "unconnected-(U$2-1-PadP$1)") (class "Default")
      (node (ref "U$2") (pin "P$1") (pinfunction "1_P$1") (pintype "bidirectional"))
    )
    (net (code "118") (name "unconnected-(U$2-2-PadP$20)") (class "Default")
      (node (ref "U$2") (pin "P$20") (pinfunction "2_P$20") (pintype "bidirectional"))
    )
    (net (code "119") (name "unconnected-(U$2-3-PadP$2)") (class "Default")
      (node (ref "U$2") (pin "P$2") (pinfunction "3_P$2") (pintype "bidirectional"))
    )
    (net (code "120") (name "unconnected-(U$2-4-PadP$19)") (class "Default")
      (node (ref "U$2") (pin "P$19") (pinfunction "4_P$19") (pintype "bidirectional"))
    )
    (net (code "121") (name "unconnected-(U$2-5-PadP$3)") (class "Default")
      (node (ref "U$2") (pin "P$3") (pinfunction "5_P$3") (pintype "bidirectional"))
    )
    (net (code "122") (name "unconnected-(U$2-6-PadP$18)") (class "Default")
      (node (ref "U$2") (pin "P$18") (pinfunction "6_P$18") (pintype "bidirectional"))
    )
    (net (code "123") (name "unconnected-(U$2-7-PadP$4)") (class "Default")
      (node (ref "U$2") (pin "P$4") (pinfunction "7_P$4") (pintype "bidirectional"))
    )
    (net (code "124") (name "unconnected-(U$2-8-PadP$17)") (class "Default")
      (node (ref "U$2") (pin "P$17") (pinfunction "8_P$17") (pintype "bidirectional"))
    )
    (net (code "125") (name "unconnected-(U$2-9-PadP$7)") (class "Default")
      (node (ref "U$2") (pin "P$7") (pinfunction "9_P$7") (pintype "bidirectional"))
    )
    (net (code "126") (name "unconnected-(U$2-10-PadP$14)") (class "Default")
      (node (ref "U$2") (pin "P$14") (pinfunction "10_P$14") (pintype "bidirectional"))
    )
    (net (code "127") (name "unconnected-(U$2-11-PadP$8)") (class "Default")
      (node (ref "U$2") (pin "P$8") (pinfunction "11_P$8") (pintype "bidirectional"))
    )
    (net (code "128") (name "unconnected-(U$2-12-PadP$13)") (class "Default")
      (node (ref "U$2") (pin "P$13") (pinfunction "12_P$13") (pintype "bidirectional"))
    )
    (net (code "129") (name "unconnected-(U$2-13-PadP$9)") (class "Default")
      (node (ref "U$2") (pin "P$9") (pinfunction "13_P$9") (pintype "bidirectional"))
    )
    (net (code "130") (name "unconnected-(U$2-14-PadP$12)") (class "Default")
      (node (ref "U$2") (pin "P$12") (pinfunction "14_P$12") (pintype "bidirectional"))
    )
    (net (code "131") (name "unconnected-(U$2-15-PadP$10)") (class "Default")
      (node (ref "U$2") (pin "P$10") (pinfunction "15_P$10") (pintype "bidirectional"))
    )
    (net (code "132") (name "unconnected-(U$2-16-PadP$11)") (class "Default")
      (node (ref "U$2") (pin "P$11") (pinfunction "16_P$11") (pintype "bidirectional"))
    )
    (net (code "133") (name "unconnected-(U$2-GND1-PadP$5)") (class "Default")
      (node (ref "U$2") (pin "P$5") (pinfunction "GND1_P$5") (pintype "bidirectional"))
    )
    (net (code "134") (name "unconnected-(U$2-GND2-PadP$6)") (class "Default")
      (node (ref "U$2") (pin "P$6") (pinfunction "GND2_P$6") (pintype "bidirectional"))
    )
    (net (code "135") (name "unconnected-(U$2-RF1-PadP$16)") (class "Default")
      (node (ref "U$2") (pin "P$16") (pinfunction "RF1_P$16") (pintype "bidirectional"))
    )
    (net (code "136") (name "unconnected-(U$2-RF2-PadP$15)") (class "Default")
      (node (ref "U$2") (pin "P$15") (pinfunction "RF2_P$15") (pintype "bidirectional"))
    )
    (net (code "137") (name "unconnected-(U$3-P$26-NA-PadP$26A)") (class "Default")
      (node (ref "U$3") (pin "P$26A") (pinfunction "P$26-NA_P$26A") (pintype "bidirectional"))
    )
    (net (code "138") (name "unconnected-(U$6-CHAN3-Pad6)") (class "Default")
      (node (ref "U$6") (pin "6") (pinfunction "CHAN3_6") (pintype "bidirectional"))
    )
    (net (code "139") (name "unconnected-(U$6-CHAN4-Pad5)") (class "Default")
      (node (ref "U$6") (pin "5") (pinfunction "CHAN4_5") (pintype "bidirectional"))
    )
    (net (code "140") (name "unconnected-(U$6-CHAN5-Pad4)") (class "Default")
      (node (ref "U$6") (pin "4") (pinfunction "CHAN5_4") (pintype "bidirectional"))
    )
    (net (code "141") (name "unconnected-(U$6-CHAN6-Pad3)") (class "Default")
      (node (ref "U$6") (pin "3") (pinfunction "CHAN6_3") (pintype "bidirectional"))
    )
    (net (code "142") (name "unconnected-(U$6-CHAN7-Pad2)") (class "Default")
      (node (ref "U$6") (pin "2") (pinfunction "CHAN7_2") (pintype "bidirectional"))
    )
    (net (code "143") (name "unconnected-(U$6-CHAN8-Pad23)") (class "Default")
      (node (ref "U$6") (pin "23") (pinfunction "CHAN8_23") (pintype "bidirectional"))
    )
    (net (code "144") (name "unconnected-(U$6-CHAN9-Pad22)") (class "Default")
      (node (ref "U$6") (pin "22") (pinfunction "CHAN9_22") (pintype "bidirectional"))
    )
    (net (code "145") (name "unconnected-(U$6-CHAN10-Pad21)") (class "Default")
      (node (ref "U$6") (pin "21") (pinfunction "CHAN10_21") (pintype "bidirectional"))
    )
    (net (code "146") (name "unconnected-(U$6-CHAN11-Pad20)") (class "Default")
      (node (ref "U$6") (pin "20") (pinfunction "CHAN11_20") (pintype "bidirectional"))
    )
    (net (code "147") (name "unconnected-(U$6-CHAN12-Pad19)") (class "Default")
      (node (ref "U$6") (pin "19") (pinfunction "CHAN12_19") (pintype "bidirectional"))
    )
    (net (code "148") (name "unconnected-(U$6-CHAN13-Pad18)") (class "Default")
      (node (ref "U$6") (pin "18") (pinfunction "CHAN13_18") (pintype "bidirectional"))
    )
    (net (code "149") (name "unconnected-(U$6-CHAN14-Pad17)") (class "Default")
      (node (ref "U$6") (pin "17") (pinfunction "CHAN14_17") (pintype "bidirectional"))
    )
    (net (code "150") (name "unconnected-(U$6-CHAN15-Pad16)") (class "Default")
      (node (ref "U$6") (pin "16") (pinfunction "CHAN15_16") (pintype "bidirectional"))
    )
  )
)
